# Infrared_Emission_Sch.net
KiCad netlist of a schematic drawn in Altium Designer
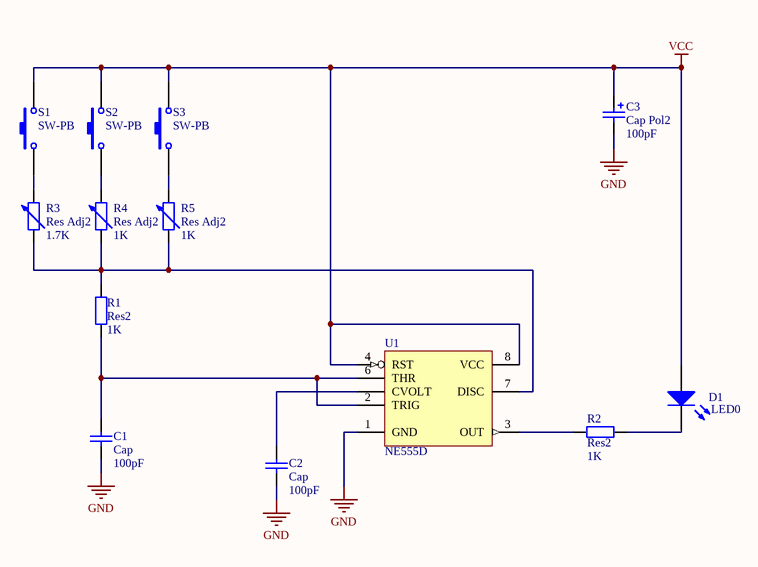
[diagram p0: Infrared Emission_Sch.SchDoc]

(export (version "E")
  (design (tool "Eeschema 10.0.6"))
  (components
    (comp (ref "C1")
      (value "Cap")
      (footprint "RAD-0.3")
      (description "Capacitor")
      (fields (field (name "ALTIUM_VALUE") "100pF") (field (name "PUBLISHER") "Altium Limited"))
      (libsource (lib "Miscellaneous Devices") (part "Cap"))
    )
    (comp (ref "C2")
      (value "Cap")
      (footprint "RAD-0.3")
      (description "Capacitor")
      (fields (field (name "ALTIUM_VALUE") "100pF") (field (name "PUBLISHER") "Altium Limited"))
      (libsource (lib "Miscellaneous Devices") (part "Cap"))
    )
    (comp (ref "C3")
      (value "Cap Pol2")
      (footprint "POLAR0.8")
      (description "Polarized Capacitor (Axial)")
      (fields (field (name "ALTIUM_VALUE") "100pF") (field (name "PUBLISHER") "Altium Limited"))
      (libsource (lib "Miscellaneous Devices") (part "Cap Pol2"))
    )
    (comp (ref "D1")
      (value "LED0")
      (footprint "LED-0")
      (description "Typical INFRARED GaAs LED")
      (fields (field (name "PUBLISHER") "Altium Limited"))
      (libsource (lib "Miscellaneous Devices") (part "LED0"))
    )
    (comp (ref "R1")
      (value "Res2")
      (footprint "AXIAL-0.4")
      (description "Resistor")
      (fields (field (name "ALTIUM_VALUE") "1K") (field (name "PUBLISHER") "Altium Limited"))
      (libsource (lib "Miscellaneous Devices") (part "Res2"))
    )
    (comp (ref "R2")
      (value "Res2")
      (footprint "AXIAL-0.4")
      (description "Resistor")
      (fields (field (name "ALTIUM_VALUE") "1K") (field (name "PUBLISHER") "Altium Limited"))
      (libsource (lib "") (part "Res2_1"))
    )
    (comp (ref "R3")
      (value "Res Adj2")
      (footprint "AXIAL-0.6")
      (description "Variable Resistor")
      (fields (field (name "ALTIUM_VALUE") "1.7K") (field (name "PUBLISHER") "Altium Limited"))
      (libsource (lib "Miscellaneous Devices") (part "Res Adj2"))
    )
    (comp (ref "R4")
      (value "Res Adj2")
      (footprint "AXIAL-0.6")
      (description "Variable Resistor")
      (fields (field (name "ALTIUM_VALUE") "1K") (field (name "PUBLISHER") "Altium Limited"))
      (libsource (lib "Miscellaneous Devices") (part "Res Adj2"))
    )
    (comp (ref "R5")
      (value "Res Adj2")
      (footprint "AXIAL-0.6")
      (description "Variable Resistor")
      (fields (field (name "ALTIUM_VALUE") "1K") (field (name "PUBLISHER") "Altium Limited"))
      (libsource (lib "Miscellaneous Devices") (part "Res Adj2"))
    )
    (comp (ref "S1")
      (value "SW-PB")
      (footprint "SPST-2")
      (description "Switch")
      (fields (field (name "PUBLISHER") "Altium Limited"))
      (libsource (lib "Miscellaneous Devices") (part "SW-PB"))
    )
    (comp (ref "S2")
      (value "SW-PB")
      (footprint "SPST-2")
      (description "Switch")
      (fields (field (name "PUBLISHER") "Altium Limited"))
      (libsource (lib "Miscellaneous Devices") (part "SW-PB"))
    )
    (comp (ref "S3")
      (value "SW-PB")
      (footprint "SPST-2")
      (description "Switch")
      (fields (field (name "PUBLISHER") "Altium Limited"))
      (libsource (lib "Miscellaneous Devices") (part "SW-PB"))
    )
    (comp (ref "U1")
      (value "NE555D")
      (footprint "D008_N")
      (description "Precision Timer")
      (fields (field (name "PUBLISHER") "Altium Limited"))
      (libsource (lib "TI Analog Timer Circuit") (part "NE555D"))
    )
  )
  (nets
    (net (code "1") (name "GND") (class "Default")
      (node (ref "C1") (pin "2") (pinfunction "2_2") (pintype "passive"))
      (node (ref "C2") (pin "2") (pinfunction "2_2") (pintype "passive"))
      (node (ref "C3") (pin "2") (pinfunction "2_2") (pintype "passive"))
      (node (ref "U1") (pin "1") (pinfunction "GND_1") (pintype "power_in"))
    )
    (net (code "2") (name "Net-(D1-K)") (class "Default")
      (node (ref "D1") (pin "2") (pinfunction "K_2") (pintype "passive"))
      (node (ref "R2") (pin "2") (pinfunction "2_2") (pintype "passive"))
    )
    (net (code "3") (name "Net-(R3-Pad2)") (class "Default")
      (node (ref "R3") (pin "2") (pinfunction "2_2") (pintype "passive"))
      (node (ref "S1") (pin "1") (pinfunction "1_1") (pintype "passive"))
    )
    (net (code "4") (name "Net-(R4-Pad2)") (class "Default")
      (node (ref "R4") (pin "2") (pinfunction "2_2") (pintype "passive"))
      (node (ref "S2") (pin "1") (pinfunction "1_1") (pintype "passive"))
    )
    (net (code "5") (name "Net-(R5-Pad2)") (class "Default")
      (node (ref "R5") (pin "2") (pinfunction "2_2") (pintype "passive"))
      (node (ref "S3") (pin "1") (pinfunction "1_1") (pintype "passive"))
    )
    (net (code "6") (name "Net-(U1-CVOLT)") (class "Default")
      (node (ref "C2") (pin "1") (pinfunction "1_1") (pintype "passive"))
      (node (ref "U1") (pin "5") (pinfunction "CVOLT_5") (pintype "passive"))
    )
    (net (code "7") (name "Net-(U1-DISC)") (class "Default")
      (node (ref "R1") (pin "2") (pinfunction "2_2") (pintype "passive"))
      (node (ref "R3") (pin "1") (pinfunction "1_1") (pintype "passive"))
      (node (ref "R4") (pin "1") (pinfunction "1_1") (pintype "passive"))
      (node (ref "R5") (pin "1") (pinfunction "1_1") (pintype "passive"))
      (node (ref "U1") (pin "7") (pinfunction "DISC_7") (pintype "open_collector"))
    )
    (net (code "8") (name "Net-(U1-OUT)") (class "Default")
      (node (ref "R2") (pin "1") (pinfunction "1_1") (pintype "passive"))
      (node (ref "U1") (pin "3") (pinfunction "OUT_3") (pintype "output"))
    )
    (net (code "9") (name "Net-(U1-THR)") (class "Default")
      (node (ref "C1") (pin "1") (pinfunction "1_1") (pintype "passive"))
      (node (ref "R1") (pin "1") (pinfunction "1_1") (pintype "passive"))
      (node (ref "U1") (pin "2") (pinfunction "TRIG_2") (pintype "passive"))
      (node (ref "U1") (pin "6") (pinfunction "THR_6") (pintype "passive"))
    )
    (net (code "10") (name "VCC") (class "Default")
      (node (ref "C3") (pin "1") (pinfunction "1_1") (pintype "passive"))
      (node (ref "D1") (pin "1") (pinfunction "A_1") (pintype "passive"))
      (node (ref "S1") (pin "2") (pinfunction "2_2") (pintype "passive"))
      (node (ref "S2") (pin "2") (pinfunction "2_2") (pintype "passive"))
      (node (ref "S3") (pin "2") (pinfunction "2_2") (pintype "passive"))
      (node (ref "U1") (pin "4") (pinfunction "RST_4") (pintype "input"))
      (node (ref "U1") (pin "8") (pinfunction "VCC_8") (pintype "power_in"))
    )
  )
)
